# am_overview.net
KiCad netlist of a schematic drawn in EAGLE
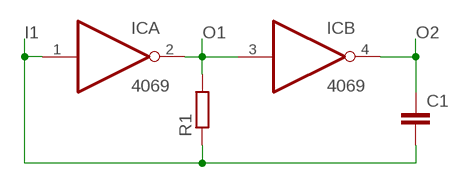
[diagram p0: schematic, sheet 1]

(export (version "E")
  (design (tool "Eeschema 10.0.6"))
  (components
    (comp (ref "C1")
      (value "C-EU025-024X044")
      (footprint "eagle-import:C025-024X044")
      (libsource (lib "eagle-import") (part "C-EU025-024X044"))
    )
    (comp (ref "IC")
      (value "4069")
      (footprint "eagle-import:DIL14")
      (libsource (lib "eagle-import") (part "4069N"))
    )
    (comp (ref "R1")
      (value "R-EU_0204/2V")
      (footprint "eagle-import:0204V")
      (libsource (lib "eagle-import") (part "R-EU_0204/2V"))
    )
  )
  (nets
    (net (code "1") (name "Net-(ICA-I)") (class "Default")
      (node (ref "C1") (pin "2") (pinfunction "2_2") (pintype "passive"))
      (node (ref "IC") (pin "1") (pinfunction "I_1") (pintype "input"))
      (node (ref "R1") (pin "1") (pinfunction "1_1") (pintype "passive"))
    )
    (net (code "2") (name "Net-(ICA-O)") (class "Default")
      (node (ref "IC") (pin "2") (pinfunction "O_2") (pintype "output"))
      (node (ref "IC") (pin "3") (pinfunction "I_3") (pintype "input"))
      (node (ref "R1") (pin "2") (pinfunction "2_2") (pintype "passive"))
    )
    (net (code "3") (name "Net-(ICB-O)") (class "Default")
      (node (ref "C1") (pin "1") (pinfunction "1_1") (pintype "passive"))
      (node (ref "IC") (pin "4") (pinfunction "O_4") (pintype "output"))
    )
  )
)
